# U_model.net
KiCad netlist of a schematic drawn in Altium Designer
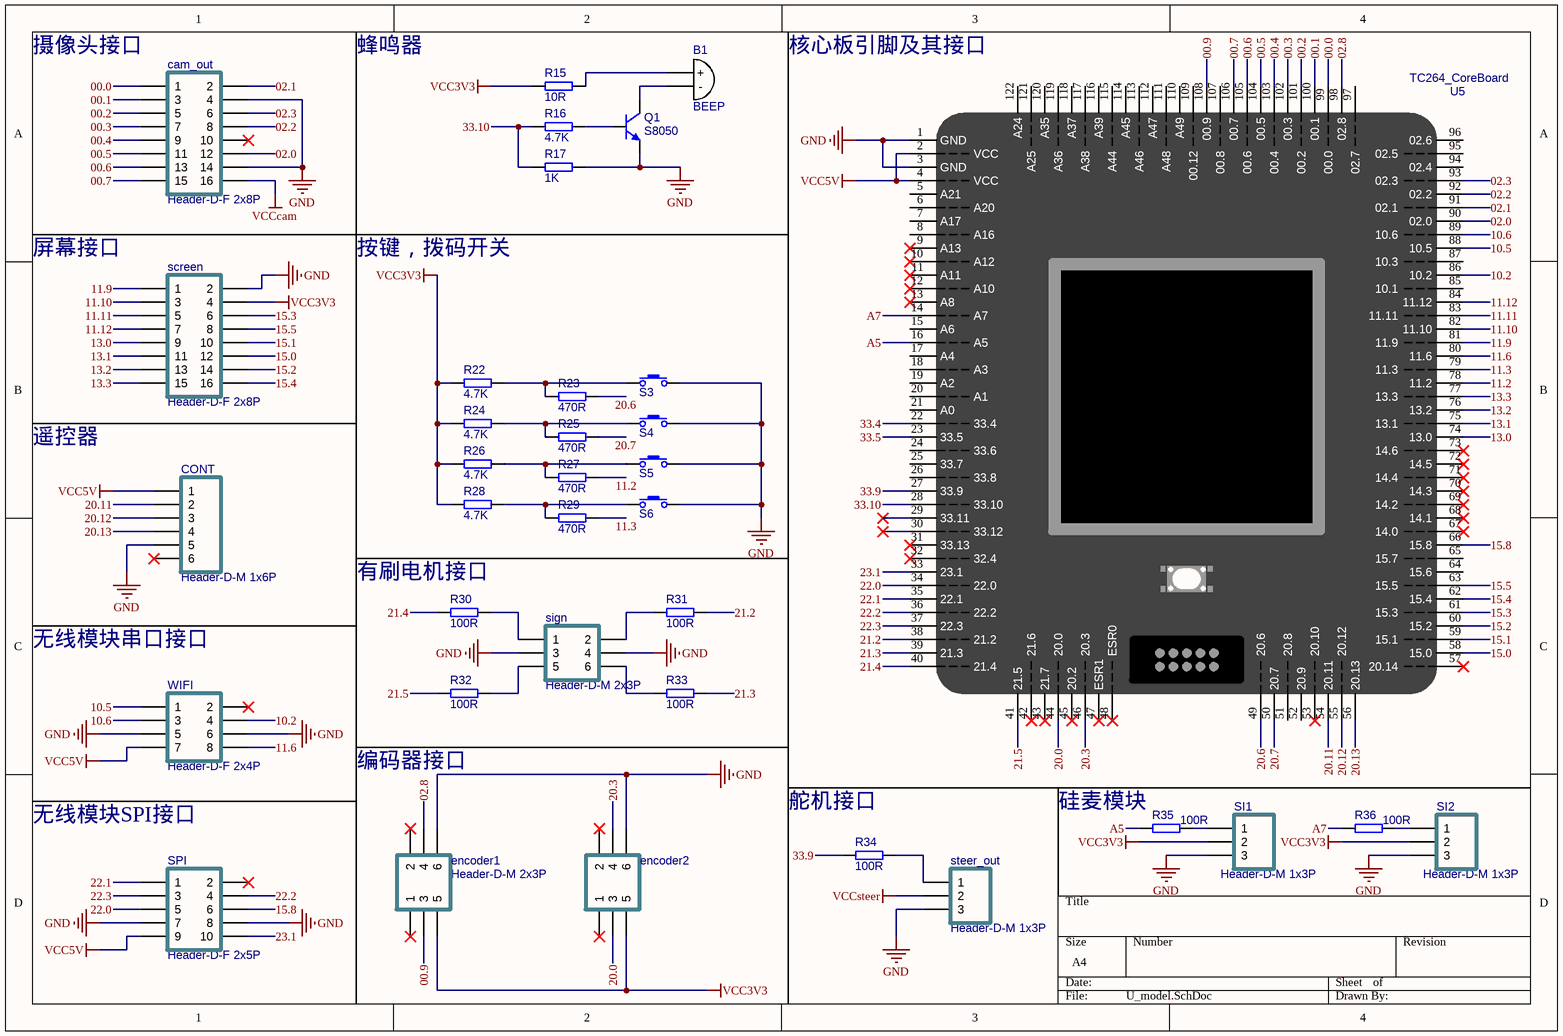
[diagram p0: U_model.SchDoc]

(export (version "E")
  (design (tool "Eeschema 10.0.6"))
  (components
    (comp (ref "B1")
      (value "BEEP")
      (footprint "BEEP 9x5.5mm")
      (description "蜂鸣器")
      (libsource (lib "TC264_主板_V2.6") (part "BEEP"))
    )
    (comp (ref "cam_out")
      (value "Header-D-F 2x8P")
      (footprint "HDR2X8-F")
      (description "2x8pin, 直插, 双排座")
      (libsource (lib "TC264_主板_V2.6") (part "Header-D-F 2x8P"))
    )
    (comp (ref "CONT")
      (value "Header-D-M 1x6P")
      (footprint "HDR1X6-M")
      (description "1x6pin, 直插, 排针")
      (libsource (lib "TC264_主板_V2.6") (part "Header-D-M 1x6P"))
    )
    (comp (ref "encoder1")
      (value "Header-D-M 2x3P")
      (footprint "HDR2X3-M")
      (description "2x3pin, 直插, 双排针")
      (libsource (lib "TC264_主板_V2.6") (part "Header-D-M 2x3P"))
    )
    (comp (ref "encoder2")
      (value "~")
      (footprint "HDR2X3-M")
      (description "2x3pin, 直插, 双排针")
      (libsource (lib "TC264_主板_V2.6") (part "Header-D-M 2x3P"))
    )
    (comp (ref "Q1")
      (value "S8050")
      (footprint "SOT-23")
      (description "NPN 三极管")
      (fields (field (name "PARTNUMBER") "S8050") (field (name "PUBLISHER") "Altium Limited"))
      (libsource (lib "TC264_主板_V2.6") (part "NPN S8050"))
    )
    (comp (ref "R15")
      (value "10R")
      (footprint "RESC1608[0603]S-N")
      (description "贴片电阻")
      (fields (field (name "POWER") "1/8W") (field (name "TOLERANCE") "±1%"))
      (libsource (lib "TC264_主板_V2.6") (part "Res-Chip_10"))
    )
    (comp (ref "R16")
      (value "4.7K")
      (footprint "RESC1608[0603]S-N")
      (description "贴片电阻")
      (fields (field (name "POWER") "1/8W") (field (name "TOLERANCE") "±1%"))
      (libsource (lib "TC264_主板_V2.6") (part "Res-Chip_3"))
    )
    (comp (ref "R17")
      (value "1K")
      (footprint "RESC1608[0603]S-N")
      (description "贴片电阻")
      (fields (field (name "POWER") "1/8W") (field (name "TOLERANCE") "±1%"))
      (libsource (lib "TC264_主板_V2.6") (part "Res-Chip_11"))
    )
    (comp (ref "R22")
      (value "4.7K")
      (footprint "RESC1608[0603]S-N")
      (description "贴片电阻")
      (fields (field (name "POWER") "1/8W") (field (name "TOLERANCE") "±1%"))
      (libsource (lib "TC264_主板_V2.6") (part "Res-Chip_3"))
    )
    (comp (ref "R23")
      (value "470R")
      (footprint "RESC1608[0603]S-N")
      (description "贴片电阻")
      (fields (field (name "POWER") "1/8W") (field (name "TOLERANCE") "±1%"))
      (libsource (lib "TC264_主板_V2.6") (part "Res-Chip_12"))
    )
    (comp (ref "R24")
      (value "4.7K")
      (footprint "RESC1608[0603]S-N")
      (description "贴片电阻")
      (fields (field (name "POWER") "1/8W") (field (name "TOLERANCE") "±1%"))
      (libsource (lib "TC264_主板_V2.6") (part "Res-Chip_3"))
    )
    (comp (ref "R25")
      (value "470R")
      (footprint "RESC1608[0603]S-N")
      (description "贴片电阻")
      (fields (field (name "POWER") "1/8W") (field (name "TOLERANCE") "±1%"))
      (libsource (lib "TC264_主板_V2.6") (part "Res-Chip_12"))
    )
    (comp (ref "R26")
      (value "4.7K")
      (footprint "RESC1608[0603]S-N")
      (description "贴片电阻")
      (fields (field (name "POWER") "1/8W") (field (name "TOLERANCE") "±1%"))
      (libsource (lib "TC264_主板_V2.6") (part "Res-Chip_3"))
    )
    (comp (ref "R27")
      (value "470R")
      (footprint "RESC1608[0603]S-N")
      (description "贴片电阻")
      (fields (field (name "POWER") "1/8W") (field (name "TOLERANCE") "±1%"))
      (libsource (lib "TC264_主板_V2.6") (part "Res-Chip_12"))
    )
    (comp (ref "R28")
      (value "4.7K")
      (footprint "RESC1608[0603]S-N")
      (description "贴片电阻")
      (fields (field (name "POWER") "1/8W") (field (name "TOLERANCE") "±1%"))
      (libsource (lib "TC264_主板_V2.6") (part "Res-Chip_3"))
    )
    (comp (ref "R29")
      (value "470R")
      (footprint "RESC1608[0603]S-N")
      (description "贴片电阻")
      (fields (field (name "POWER") "1/8W") (field (name "TOLERANCE") "±1%"))
      (libsource (lib "TC264_主板_V2.6") (part "Res-Chip_12"))
    )
    (comp (ref "R30")
      (value "100R")
      (footprint "RESC1608[0603]S-N")
      (description "贴片电阻")
      (fields (field (name "POWER") "1/8W") (field (name "TOLERANCE") "±1%"))
      (libsource (lib "TC264_主板_V2.6") (part "Res-Chip_9"))
    )
    (comp (ref "R31")
      (value "100R")
      (footprint "RESC1608[0603]S-N")
      (description "贴片电阻")
      (fields (field (name "POWER") "1/8W") (field (name "TOLERANCE") "±1%"))
      (libsource (lib "TC264_主板_V2.6") (part "Res-Chip_9"))
    )
    (comp (ref "R32")
      (value "100R")
      (footprint "RESC1608[0603]S-N")
      (description "贴片电阻")
      (fields (field (name "POWER") "1/8W") (field (name "TOLERANCE") "±1%"))
      (libsource (lib "TC264_主板_V2.6") (part "Res-Chip_9"))
    )
    (comp (ref "R33")
      (value "100R")
      (footprint "RESC1608[0603]S-N")
      (description "贴片电阻")
      (fields (field (name "POWER") "1/8W") (field (name "TOLERANCE") "±1%"))
      (libsource (lib "TC264_主板_V2.6") (part "Res-Chip_9"))
    )
    (comp (ref "R34")
      (value "100R")
      (footprint "RESC1608[0603]S-N")
      (description "贴片电阻")
      (fields (field (name "POWER") "1/8W") (field (name "TOLERANCE") "±1%"))
      (libsource (lib "TC264_主板_V2.6") (part "Res-Chip_9"))
    )
    (comp (ref "R35")
      (value "100R")
      (footprint "RESC1608[0603]S-N")
      (description "贴片电阻")
      (fields (field (name "POWER") "1/8W") (field (name "TOLERANCE") "±1%"))
      (libsource (lib "TC264_主板_V2.6") (part "Res-Chip_9"))
    )
    (comp (ref "R36")
      (value "100R")
      (footprint "RESC1608[0603]S-N")
      (description "贴片电阻")
      (fields (field (name "POWER") "1/8W") (field (name "TOLERANCE") "±1%"))
      (libsource (lib "TC264_主板_V2.6") (part "Res-Chip_9"))
    )
    (comp (ref "S3")
      (value "Button")
      (footprint "PTS810-3*4-CurvePin")
      (description "按键")
      (fields (field (name "PUBLISHER") "Altium Limited"))
      (libsource (lib "TC264_主板_V2.6") (part "KEY"))
    )
    (comp (ref "S4")
      (value "Button")
      (footprint "PTS810-3*4-CurvePin")
      (description "按键")
      (fields (field (name "PUBLISHER") "Altium Limited"))
      (libsource (lib "TC264_主板_V2.6") (part "KEY"))
    )
    (comp (ref "S5")
      (value "Button")
      (footprint "PTS810-3*4-CurvePin")
      (description "按键")
      (fields (field (name "PUBLISHER") "Altium Limited"))
      (libsource (lib "TC264_主板_V2.6") (part "KEY"))
    )
    (comp (ref "S6")
      (value "Button")
      (footprint "PTS810-3*4-CurvePin")
      (description "按键")
      (fields (field (name "PUBLISHER") "Altium Limited"))
      (libsource (lib "TC264_主板_V2.6") (part "KEY"))
    )
    (comp (ref "screen")
      (value "Header-D-F 2x8P")
      (footprint "HDR2X8-F")
      (description "2x8pin, 直插, 双排座")
      (libsource (lib "TC264_主板_V2.6") (part "Header-D-F 2x8P"))
    )
    (comp (ref "SI1")
      (value "Header-D-M 1x3P")
      (footprint "HDR1X3-M")
      (description "1x3pin, 直插, 排针")
      (libsource (lib "TC264_主板_V2.6") (part "Header-D-M 1x3P"))
    )
    (comp (ref "SI2")
      (value "Header-D-M 1x3P")
      (footprint "HDR1X3-M")
      (description "1x3pin, 直插, 排针")
      (libsource (lib "TC264_主板_V2.6") (part "Header-D-M 1x3P"))
    )
    (comp (ref "sign")
      (value "Header-D-M 2x3P")
      (footprint "HDR2X3-M")
      (description "2x3pin, 直插, 双排针")
      (libsource (lib "") (part "Header-D-M 2x3P_1"))
    )
    (comp (ref "SPI")
      (value "Header-D-F 2x5P")
      (footprint "HDR2X5-F")
      (description "2x5pin, 直插, 双排座")
      (libsource (lib "TC264_主板_V2.6") (part "Header-D-F 2x5P"))
    )
    (comp (ref "steer_out")
      (value "Header-D-M 1x3P")
      (footprint "HDR1X3-M")
      (description "1x3pin, 直插, 排针")
      (libsource (lib "TC264_主板_V2.6") (part "Header-D-M 1x3P"))
    )
    (comp (ref "U5")
      (value "TC264_CoreBoard")
      (footprint "TC264_CoreBoard")
      (description "逐飞科技TC264核心板")
      (libsource (lib "TC264_主板_V2.6") (part "TC264_CoreBoard"))
    )
    (comp (ref "WIFI")
      (value "Header-D-F 2x4P")
      (footprint "HDR2X4-F")
      (description "2x4pin, 直插, 双排座")
      (libsource (lib "TC264_主板_V2.6") (part "Header-D-F 2x4P"))
    )
  )
  (nets
    (net (code "1") (name "/00.0") (class "Default")
      (node (ref "U5") (pin "99") (pinfunction "00.0_99") (pintype "passive"))
      (node (ref "cam_out") (pin "1") (pinfunction "1_1") (pintype "passive"))
    )
    (net (code "2") (name "/00.1") (class "Default")
      (node (ref "U5") (pin "100") (pinfunction "00.1_100") (pintype "passive"))
      (node (ref "cam_out") (pin "3") (pinfunction "3_3") (pintype "passive"))
    )
    (net (code "3") (name "/00.2") (class "Default")
      (node (ref "U5") (pin "101") (pinfunction "00.2_101") (pintype "passive"))
      (node (ref "cam_out") (pin "5") (pinfunction "5_5") (pintype "passive"))
    )
    (net (code "4") (name "/00.3") (class "Default")
      (node (ref "U5") (pin "102") (pinfunction "00.3_102") (pintype "passive"))
      (node (ref "cam_out") (pin "7") (pinfunction "7_7") (pintype "passive"))
    )
    (net (code "5") (name "/00.4") (class "Default")
      (node (ref "U5") (pin "103") (pinfunction "00.4_103") (pintype "passive"))
      (node (ref "cam_out") (pin "9") (pinfunction "9_9") (pintype "passive"))
    )
    (net (code "6") (name "/00.5") (class "Default")
      (node (ref "U5") (pin "104") (pinfunction "00.5_104") (pintype "passive"))
      (node (ref "cam_out") (pin "11") (pinfunction "11_11") (pintype "passive"))
    )
    (net (code "7") (name "/00.6") (class "Default")
      (node (ref "U5") (pin "105") (pinfunction "00.6_105") (pintype "passive"))
      (node (ref "cam_out") (pin "13") (pinfunction "13_13") (pintype "passive"))
    )
    (net (code "8") (name "/00.7") (class "Default")
      (node (ref "U5") (pin "106") (pinfunction "00.7_106") (pintype "passive"))
      (node (ref "cam_out") (pin "15") (pinfunction "15_15") (pintype "passive"))
    )
    (net (code "9") (name "/00.9") (class "Default")
      (node (ref "U5") (pin "108") (pinfunction "00.9_108") (pintype "passive"))
      (node (ref "encoder1") (pin "3") (pinfunction "3_3") (pintype "passive"))
    )
    (net (code "10") (name "/02.0") (class "Default")
      (node (ref "U5") (pin "90") (pinfunction "02.0_90") (pintype "passive"))
      (node (ref "cam_out") (pin "12") (pinfunction "12_12") (pintype "passive"))
    )
    (net (code "11") (name "/02.1") (class "Default")
      (node (ref "U5") (pin "91") (pinfunction "02.1_91") (pintype "passive"))
      (node (ref "cam_out") (pin "2") (pinfunction "2_2") (pintype "passive"))
    )
    (net (code "12") (name "/02.2") (class "Default")
      (node (ref "U5") (pin "92") (pinfunction "02.2_92") (pintype "passive"))
      (node (ref "cam_out") (pin "8") (pinfunction "8_8") (pintype "passive"))
    )
    (net (code "13") (name "/02.3") (class "Default")
      (node (ref "U5") (pin "93") (pinfunction "02.3_93") (pintype "passive"))
      (node (ref "cam_out") (pin "6") (pinfunction "6_6") (pintype "passive"))
    )
    (net (code "14") (name "/02.8") (class "Default")
      (node (ref "U5") (pin "98") (pinfunction "02.8_98") (pintype "passive"))
      (node (ref "encoder1") (pin "4") (pinfunction "4_4") (pintype "passive"))
    )
    (net (code "15") (name "/10.2") (class "Default")
      (node (ref "U5") (pin "86") (pinfunction "10.2_86") (pintype "passive"))
      (node (ref "WIFI") (pin "4") (pinfunction "4_4") (pintype "passive"))
    )
    (net (code "16") (name "/10.5") (class "Default")
      (node (ref "U5") (pin "88") (pinfunction "10.5_88") (pintype "passive"))
      (node (ref "WIFI") (pin "1") (pinfunction "1_1") (pintype "passive"))
    )
    (net (code "17") (name "/10.6") (class "Default")
      (node (ref "U5") (pin "89") (pinfunction "10.6_89") (pintype "passive"))
      (node (ref "WIFI") (pin "3") (pinfunction "3_3") (pintype "passive"))
    )
    (net (code "18") (name "/11.2") (class "Default")
      (node (ref "R27") (pin "2") (pinfunction "2_2") (pintype "passive"))
      (node (ref "U5") (pin "78") (pinfunction "11.2_78") (pintype "passive"))
    )
    (net (code "19") (name "/11.3") (class "Default")
      (node (ref "R29") (pin "2") (pinfunction "2_2") (pintype "passive"))
      (node (ref "U5") (pin "79") (pinfunction "11.3_79") (pintype "passive"))
    )
    (net (code "20") (name "/11.6") (class "Default")
      (node (ref "U5") (pin "80") (pinfunction "11.6_80") (pintype "passive"))
      (node (ref "WIFI") (pin "8") (pinfunction "8_8") (pintype "passive"))
    )
    (net (code "21") (name "/11.9") (class "Default")
      (node (ref "U5") (pin "81") (pinfunction "11.9_81") (pintype "passive"))
      (node (ref "screen") (pin "1") (pinfunction "1_1") (pintype "passive"))
    )
    (net (code "22") (name "/11.10") (class "Default")
      (node (ref "U5") (pin "82") (pinfunction "11.10_82") (pintype "passive"))
      (node (ref "screen") (pin "3") (pinfunction "3_3") (pintype "passive"))
    )
    (net (code "23") (name "/11.11") (class "Default")
      (node (ref "U5") (pin "83") (pinfunction "11.11_83") (pintype "passive"))
      (node (ref "screen") (pin "5") (pinfunction "5_5") (pintype "passive"))
    )
    (net (code "24") (name "/11.12") (class "Default")
      (node (ref "U5") (pin "84") (pinfunction "11.12_84") (pintype "passive"))
      (node (ref "screen") (pin "7") (pinfunction "7_7") (pintype "passive"))
    )
    (net (code "25") (name "/13.0") (class "Default")
      (node (ref "U5") (pin "74") (pinfunction "13.0_74") (pintype "passive"))
      (node (ref "screen") (pin "9") (pinfunction "9_9") (pintype "passive"))
    )
    (net (code "26") (name "/13.1") (class "Default")
      (node (ref "U5") (pin "75") (pinfunction "13.1_75") (pintype "passive"))
      (node (ref "screen") (pin "11") (pinfunction "11_11") (pintype "passive"))
    )
    (net (code "27") (name "/13.2") (class "Default")
      (node (ref "U5") (pin "76") (pinfunction "13.2_76") (pintype "passive"))
      (node (ref "screen") (pin "13") (pinfunction "13_13") (pintype "passive"))
    )
    (net (code "28") (name "/13.3") (class "Default")
      (node (ref "U5") (pin "77") (pinfunction "13.3_77") (pintype "passive"))
      (node (ref "screen") (pin "15") (pinfunction "15_15") (pintype "passive"))
    )
    (net (code "29") (name "/15.0") (class "Default")
      (node (ref "U5") (pin "58") (pinfunction "15.0_58") (pintype "passive"))
      (node (ref "screen") (pin "12") (pinfunction "12_12") (pintype "passive"))
    )
    (net (code "30") (name "/15.1") (class "Default")
      (node (ref "U5") (pin "59") (pinfunction "15.1_59") (pintype "passive"))
      (node (ref "screen") (pin "10") (pinfunction "10_10") (pintype "passive"))
    )
    (net (code "31") (name "/15.2") (class "Default")
      (node (ref "U5") (pin "60") (pinfunction "15.2_60") (pintype "passive"))
      (node (ref "screen") (pin "14") (pinfunction "14_14") (pintype "passive"))
    )
    (net (code "32") (name "/15.3") (class "Default")
      (node (ref "U5") (pin "61") (pinfunction "15.3_61") (pintype "passive"))
      (node (ref "screen") (pin "6") (pinfunction "6_6") (pintype "passive"))
    )
    (net (code "33") (name "/15.4") (class "Default")
      (node (ref "U5") (pin "62") (pinfunction "15.4_62") (pintype "passive"))
      (node (ref "screen") (pin "16") (pinfunction "16_16") (pintype "passive"))
    )
    (net (code "34") (name "/15.5") (class "Default")
      (node (ref "U5") (pin "63") (pinfunction "15.5_63") (pintype "passive"))
      (node (ref "screen") (pin "8") (pinfunction "8_8") (pintype "passive"))
    )
    (net (code "35") (name "/15.8") (class "Default")
      (node (ref "SPI") (pin "6") (pinfunction "6_6") (pintype "passive"))
      (node (ref "U5") (pin "66") (pinfunction "15.8_66") (pintype "passive"))
    )
    (net (code "36") (name "/20.0") (class "Default")
      (node (ref "U5") (pin "44") (pinfunction "20.0_44") (pintype "passive"))
      (node (ref "encoder2") (pin "3") (pinfunction "3_3") (pintype "passive"))
    )
    (net (code "37") (name "/20.3") (class "Default")
      (node (ref "U5") (pin "46") (pinfunction "20.3_46") (pintype "passive"))
      (node (ref "encoder2") (pin "4") (pinfunction "4_4") (pintype "passive"))
    )
    (net (code "38") (name "/20.6") (class "Default")
      (node (ref "R23") (pin "2") (pinfunction "2_2") (pintype "passive"))
      (node (ref "U5") (pin "49") (pinfunction "20.6_49") (pintype "passive"))
    )
    (net (code "39") (name "/20.7") (class "Default")
      (node (ref "R25") (pin "2") (pinfunction "2_2") (pintype "passive"))
      (node (ref "U5") (pin "50") (pinfunction "20.7_50") (pintype "passive"))
    )
    (net (code "40") (name "/20.11") (class "Default")
      (node (ref "CONT") (pin "2") (pinfunction "2_2") (pintype "passive"))
      (node (ref "U5") (pin "54") (pinfunction "20.11_54") (pintype "passive"))
    )
    (net (code "41") (name "/20.12") (class "Default")
      (node (ref "CONT") (pin "3") (pinfunction "3_3") (pintype "passive"))
      (node (ref "U5") (pin "55") (pinfunction "20.12_55") (pintype "passive"))
    )
    (net (code "42") (name "/20.13") (class "Default")
      (node (ref "CONT") (pin "4") (pinfunction "4_4") (pintype "passive"))
      (node (ref "U5") (pin "56") (pinfunction "20.13_56") (pintype "passive"))
    )
    (net (code "43") (name "/21.2") (class "Default")
      (node (ref "R31") (pin "2") (pinfunction "2_2") (pintype "passive"))
      (node (ref "U5") (pin "38") (pinfunction "21.2_38") (pintype "passive"))
    )
    (net (code "44") (name "/21.3") (class "Default")
      (node (ref "R33") (pin "2") (pinfunction "2_2") (pintype "passive"))
      (node (ref "U5") (pin "39") (pinfunction "21.3_39") (pintype "passive"))
    )
    (net (code "45") (name "/21.4") (class "Default")
      (node (ref "R30") (pin "1") (pinfunction "1_1") (pintype "passive"))
      (node (ref "U5") (pin "40") (pinfunction "21.4_40") (pintype "passive"))
    )
    (net (code "46") (name "/21.5") (class "Default")
      (node (ref "R32") (pin "1") (pinfunction "1_1") (pintype "passive"))
      (node (ref "U5") (pin "41") (pinfunction "21.5_41") (pintype "passive"))
    )
    (net (code "47") (name "/22.0") (class "Default")
      (node (ref "SPI") (pin "5") (pinfunction "5_5") (pintype "passive"))
      (node (ref "U5") (pin "34") (pinfunction "22.0_34") (pintype "passive"))
    )
    (net (code "48") (name "/22.1") (class "Default")
      (node (ref "SPI") (pin "1") (pinfunction "1_1") (pintype "passive"))
      (node (ref "U5") (pin "35") (pinfunction "22.1_35") (pintype "passive"))
    )
    (net (code "49") (name "/22.2") (class "Default")
      (node (ref "SPI") (pin "4") (pinfunction "4_4") (pintype "passive"))
      (node (ref "U5") (pin "36") (pinfunction "22.2_36") (pintype "passive"))
    )
    (net (code "50") (name "/22.3") (class "Default")
      (node (ref "SPI") (pin "3") (pinfunction "3_3") (pintype "passive"))
      (node (ref "U5") (pin "37") (pinfunction "22.3_37") (pintype "passive"))
    )
    (net (code "51") (name "/23.1") (class "Default")
      (node (ref "SPI") (pin "10") (pinfunction "10_10") (pintype "passive"))
      (node (ref "U5") (pin "33") (pinfunction "23.1_33") (pintype "passive"))
    )
    (net (code "52") (name "/33.4") (class "Default")
      (node (ref "U5") (pin "22") (pinfunction "33.4_22") (pintype "passive"))
    )
    (net (code "53") (name "/33.5") (class "Default")
      (node (ref "U5") (pin "23") (pinfunction "33.5_23") (pintype "passive"))
    )
    (net (code "54") (name "/33.9") (class "Default")
      (node (ref "R34") (pin "1") (pinfunction "1_1") (pintype "passive"))
      (node (ref "U5") (pin "27") (pinfunction "33.9_27") (pintype "passive"))
    )
    (net (code "55") (name "/33.10") (class "Default")
      (node (ref "R16") (pin "1") (pinfunction "1_1") (pintype "passive"))
      (node (ref "R17") (pin "1") (pinfunction "1_1") (pintype "passive"))
      (node (ref "U5") (pin "28") (pinfunction "33.10_28") (pintype "passive"))
    )
    (net (code "56") (name "/A5") (class "Default")
      (node (ref "R35") (pin "1") (pinfunction "1_1") (pintype "passive"))
      (node (ref "U5") (pin "16") (pinfunction "A5_16") (pintype "passive"))
    )
    (net (code "57") (name "/A7") (class "Default")
      (node (ref "R36") (pin "1") (pinfunction "1_1") (pintype "passive"))
      (node (ref "U5") (pin "14") (pinfunction "A7_14") (pintype "passive"))
    )
    (net (code "58") (name "GND") (class "Default")
      (node (ref "CONT") (pin "5") (pinfunction "5_5") (pintype "passive"))
      (node (ref "Q1") (pin "2") (pinfunction "E_2") (pintype "passive"))
      (node (ref "R17") (pin "2") (pinfunction "2_2") (pintype "passive"))
      (node (ref "S3") (pin "1") (pinfunction "1_1") (pintype "passive"))
      (node (ref "S4") (pin "1") (pinfunction "1_1") (pintype "passive"))
      (node (ref "S5") (pin "1") (pinfunction "1_1") (pintype "passive"))
      (node (ref "S6") (pin "1") (pinfunction "1_1") (pintype "passive"))
      (node (ref "SI1") (pin "3") (pinfunction "3_3") (pintype "passive"))
      (node (ref "SI2") (pin "3") (pinfunction "3_3") (pintype "passive"))
      (node (ref "SPI") (pin "7") (pinfunction "7_7") (pintype "passive"))
      (node (ref "SPI") (pin "8") (pinfunction "8_8") (pintype "passive"))
      (node (ref "U5") (pin "1") (pinfunction "GND_1") (pintype "passive"))
      (node (ref "U5") (pin "3") (pinfunction "GND_3") (pintype "passive"))
      (node (ref "WIFI") (pin "5") (pinfunction "5_5") (pintype "passive"))
      (node (ref "WIFI") (pin "6") (pinfunction "6_6") (pintype "passive"))
      (node (ref "cam_out") (pin "14") (pinfunction "14_14") (pintype "passive"))
      (node (ref "cam_out") (pin "4") (pinfunction "4_4") (pintype "passive"))
      (node (ref "encoder1") (pin "6") (pinfunction "6_6") (pintype "passive"))
      (node (ref "encoder2") (pin "6") (pinfunction "6_6") (pintype "passive"))
      (node (ref "screen") (pin "2") (pinfunction "2_2") (pintype "passive"))
      (node (ref "sign") (pin "3") (pinfunction "3_3") (pintype "passive"))
      (node (ref "sign") (pin "4") (pinfunction "4_4") (pintype "passive"))
      (node (ref "steer_out") (pin "3") (pinfunction "3_3") (pintype "passive"))
    )
    (net (code "59") (name "Net-(B1-+)") (class "Default")
      (node (ref "B1") (pin "1") (pinfunction "+_1") (pintype "passive"))
      (node (ref "R15") (pin "2") (pinfunction "2_2") (pintype "passive"))
    )
    (net (code "60") (name "Net-(B1--)") (class "Default")
      (node (ref "B1") (pin "2") (pinfunction "-_2") (pintype "passive"))
      (node (ref "Q1") (pin "3") (pinfunction "C_3") (pintype "passive"))
    )
    (net (code "61") (name "Net-(Q1-B)") (class "Default")
      (node (ref "Q1") (pin "1") (pinfunction "B_1") (pintype "passive"))
      (node (ref "R16") (pin "2") (pinfunction "2_2") (pintype "passive"))
    )
    (net (code "62") (name "Net-(R22-Pad2)") (class "Default")
      (node (ref "R22") (pin "2") (pinfunction "2_2") (pintype "passive"))
      (node (ref "R23") (pin "1") (pinfunction "1_1") (pintype "passive"))
      (node (ref "S3") (pin "2") (pinfunction "2_2") (pintype "passive"))
    )
    (net (code "63") (name "Net-(R24-Pad2)") (class "Default")
      (node (ref "R24") (pin "2") (pinfunction "2_2") (pintype "passive"))
      (node (ref "R25") (pin "1") (pinfunction "1_1") (pintype "passive"))
      (node (ref "S4") (pin "2") (pinfunction "2_2") (pintype "passive"))
    )
    (net (code "64") (name "Net-(R26-Pad2)") (class "Default")
      (node (ref "R26") (pin "2") (pinfunction "2_2") (pintype "passive"))
      (node (ref "R27") (pin "1") (pinfunction "1_1") (pintype "passive"))
      (node (ref "S5") (pin "2") (pinfunction "2_2") (pintype "passive"))
    )
    (net (code "65") (name "Net-(R28-Pad2)") (class "Default")
      (node (ref "R28") (pin "2") (pinfunction "2_2") (pintype "passive"))
      (node (ref "R29") (pin "1") (pinfunction "1_1") (pintype "passive"))
      (node (ref "S6") (pin "2") (pinfunction "2_2") (pintype "passive"))
    )
    (net (code "66") (name "Net-(R30-Pad2)") (class "Default")
      (node (ref "R30") (pin "2") (pinfunction "2_2") (pintype "passive"))
      (node (ref "sign") (pin "1") (pinfunction "1_1") (pintype "passive"))
    )
    (net (code "67") (name "Net-(R31-Pad1)") (class "Default")
      (node (ref "R31") (pin "1") (pinfunction "1_1") (pintype "passive"))
      (node (ref "sign") (pin "2") (pinfunction "2_2") (pintype "passive"))
    )
    (net (code "68") (name "Net-(R32-Pad2)") (class "Default")
      (node (ref "R32") (pin "2") (pinfunction "2_2") (pintype "passive"))
      (node (ref "sign") (pin "5") (pinfunction "5_5") (pintype "passive"))
    )
    (net (code "69") (name "Net-(R33-Pad1)") (class "Default")
      (node (ref "R33") (pin "1") (pinfunction "1_1") (pintype "passive"))
      (node (ref "sign") (pin "6") (pinfunction "6_6") (pintype "passive"))
    )
    (net (code "70") (name "Net-(R34-Pad2)") (class "Default")
      (node (ref "R34") (pin "2") (pinfunction "2_2") (pintype "passive"))
      (node (ref "steer_out") (pin "1") (pinfunction "1_1") (pintype "passive"))
    )
    (net (code "71") (name "Net-(R35-Pad2)") (class "Default")
      (node (ref "R35") (pin "2") (pinfunction "2_2") (pintype "passive"))
      (node (ref "SI1") (pin "1") (pinfunction "1_1") (pintype "passive"))
    )
    (net (code "72") (name "Net-(R36-Pad2)") (class "Default")
      (node (ref "R36") (pin "2") (pinfunction "2_2") (pintype "passive"))
      (node (ref "SI2") (pin "1") (pinfunction "1_1") (pintype "passive"))
    )
    (net (code "73") (name "VCC3V3") (class "Default")
      (node (ref "R15") (pin "1") (pinfunction "1_1") (pintype "passive"))
      (node (ref "R22") (pin "1") (pinfunction "1_1") (pintype "passive"))
      (node (ref "R24") (pin "1") (pinfunction "1_1") (pintype "passive"))
      (node (ref "R26") (pin "1") (pinfunction "1_1") (pintype "passive"))
      (node (ref "R28") (pin "1") (pinfunction "1_1") (pintype "passive"))
      (node (ref "SI1") (pin "2") (pinfunction "2_2") (pintype "passive"))
      (node (ref "SI2") (pin "2") (pinfunction "2_2") (pintype "passive"))
      (node (ref "encoder1") (pin "5") (pinfunction "5_5") (pintype "passive"))
      (node (ref "encoder2") (pin "5") (pinfunction "5_5") (pintype "passive"))
      (node (ref "screen") (pin "4") (pinfunction "4_4") (pintype "passive"))
    )
    (net (code "74") (name "VCC5V") (class "Default")
      (node (ref "CONT") (pin "1") (pinfunction "1_1") (pintype "passive"))
      (node (ref "SPI") (pin "9") (pinfunction "9_9") (pintype "passive"))
      (node (ref "U5") (pin "2") (pinfunction "VCC_2") (pintype "passive"))
      (node (ref "U5") (pin "4") (pinfunction "VCC_4") (pintype "passive"))
      (node (ref "WIFI") (pin "7") (pinfunction "7_7") (pintype "passive"))
    )
    (net (code "75") (name "VCCcam") (class "Default")
      (node (ref "cam_out") (pin "16") (pinfunction "16_16") (pintype "passive"))
    )
    (net (code "76") (name "VCCsteer") (class "Default")
      (node (ref "steer_out") (pin "2") (pinfunction "2_2") (pintype "passive"))
    )
    (net (code "77") (name "unconnected-(CONT-Pad6)") (class "Default")
      (node (ref "CONT") (pin "6") (pinfunction "6_6") (pintype "passive+no_connect"))
    )
    (net (code "78") (name "unconnected-(SPI-Pad2)") (class "Default")
      (node (ref "SPI") (pin "2") (pinfunction "2_2") (pintype "passive+no_connect"))
    )
    (net (code "79") (name "unconnected-(U5-00.8-Pad107)") (class "Default")
      (node (ref "U5") (pin "107") (pinfunction "00.8_107") (pintype "passive"))
    )
    (net (code "80") (name "unconnected-(U5-00.12-Pad109)") (class "Default")
      (node (ref "U5") (pin "109") (pinfunction "00.12_109") (pintype "passive"))
    )
    (net (code "81") (name "unconnected-(U5-02.4-Pad94)") (class "Default")
      (node (ref "U5") (pin "94") (pinfunction "02.4_94") (pintype "passive"))
    )
    (net (code "82") (name "unconnected-(U5-02.5-Pad95)") (class "Default")
      (node (ref "U5") (pin "95") (pinfunction "02.5_95") (pintype "passive"))
    )
    (net (code "83") (name "unconnected-(U5-02.6-Pad96)") (class "Default")
      (node (ref "U5") (pin "96") (pinfunction "02.6_96") (pintype "passive"))
    )
    (net (code "84") (name "unconnected-(U5-02.7-Pad97)") (class "Default")
      (node (ref "U5") (pin "97") (pinfunction "02.7_97") (pintype "passive"))
    )
    (net (code "85") (name "unconnected-(U5-10.1-Pad85)") (class "Default")
      (node (ref "U5") (pin "85") (pinfunction "10.1_85") (pintype "passive"))
    )
    (net (code "86") (name "unconnected-(U5-10.3-Pad87)") (class "Default")
      (node (ref "U5") (pin "87") (pinfunction "10.3_87") (pintype "passive"))
    )
    (net (code "87") (name "unconnected-(U5-14.0-Pad67)") (class "Default")
      (node (ref "U5") (pin "67") (pinfunction "14.0_67") (pintype "passive+no_connect"))
    )
    (net (code "88") (name "unconnected-(U5-14.1-Pad68)") (class "Default")
      (node (ref "U5") (pin "68") (pinfunction "14.1_68") (pintype "passive+no_connect"))
    )
    (net (code "89") (name "unconnected-(U5-14.2-Pad69)") (class "Default")
      (node (ref "U5") (pin "69") (pinfunction "14.2_69") (pintype "passive+no_connect"))
    )
    (net (code "90") (name "unconnected-(U5-14.3-Pad70)") (class "Default")
      (node (ref "U5") (pin "70") (pinfunction "14.3_70") (pintype "passive+no_connect"))
    )
    (net (code "91") (name "unconnected-(U5-14.4-Pad71)") (class "Default")
      (node (ref "U5") (pin "71") (pinfunction "14.4_71") (pintype "passive+no_connect"))
    )
    (net (code "92") (name "unconnected-(U5-14.5-Pad72)") (class "Default")
      (node (ref "U5") (pin "72") (pinfunction "14.5_72") (pintype "passive+no_connect"))
    )
    (net (code "93") (name "unconnected-(U5-14.6-Pad73)") (class "Default")
      (node (ref "U5") (pin "73") (pinfunction "14.6_73") (pintype "passive+no_connect"))
    )
    (net (code "94") (name "unconnected-(U5-15.6-Pad64)") (class "Default")
      (node (ref "U5") (pin "64") (pinfunction "15.6_64") (pintype "passive"))
    )
    (net (code "95") (name "unconnected-(U5-15.7-Pad65)") (class "Default")
      (node (ref "U5") (pin "65") (pinfunction "15.7_65") (pintype "passive"))
    )
    (net (code "96") (name "unconnected-(U5-20.2-Pad45)") (class "Default")
      (node (ref "U5") (pin "45") (pinfunction "20.2_45") (pintype "passive+no_connect"))
    )
    (net (code "97") (name "unconnected-(U5-20.8-Pad51)") (class "Default")
      (node (ref "U5") (pin "51") (pinfunction "20.8_51") (pintype "passive"))
    )
    (net (code "98") (name "unconnected-(U5-20.9-Pad52)") (class "Default")
      (node (ref "U5") (pin "52") (pinfunction "20.9_52") (pintype "passive"))
    )
    (net (code "99") (name "unconnected-(U5-20.10-Pad53)") (class "Default")
      (node (ref "U5") (pin "53") (pinfunction "20.10_53") (pintype "passive+no_connect"))
    )
    (net (code "100") (name "unconnected-(U5-20.14-Pad57)") (class "Default")
      (node (ref "U5") (pin "57") (pinfunction "20.14_57") (pintype "passive+no_connect"))
    )
    (net (code "101") (name "unconnected-(U5-21.6-Pad42)") (class "Default")
      (node (ref "U5") (pin "42") (pinfunction "21.6_42") (pintype "passive+no_connect"))
    )
    (net (code "102") (name "unconnected-(U5-21.7-Pad43)") (class "Default")
      (node (ref "U5") (pin "43") (pinfunction "21.7_43") (pintype "passive+no_connect"))
    )
    (net (code "103") (name "unconnected-(U5-32.4-Pad32)") (class "Default")
      (node (ref "U5") (pin "32") (pinfunction "32.4_32") (pintype "passive+no_connect"))
    )
    (net (code "104") (name "unconnected-(U5-33.6-Pad24)") (class "Default")
      (node (ref "U5") (pin "24") (pinfunction "33.6_24") (pintype "passive"))
    )
    (net (code "105") (name "unconnected-(U5-33.7-Pad25)") (class "Default")
      (node (ref "U5") (pin "25") (pinfunction "33.7_25") (pintype "passive"))
    )
    (net (code "106") (name "unconnected-(U5-33.8-Pad26)") (class "Default")
      (node (ref "U5") (pin "26") (pinfunction "33.8_26") (pintype "passive"))
    )
    (net (code "107") (name "unconnected-(U5-33.11-Pad29)") (class "Default")
      (node (ref "U5") (pin "29") (pinfunction "33.11_29") (pintype "passive+no_connect"))
    )
    (net (code "108") (name "unconnected-(U5-33.12-Pad30)") (class "Default")
      (node (ref "U5") (pin "30") (pinfunction "33.12_30") (pintype "passive+no_connect"))
    )
    (net (code "109") (name "unconnected-(U5-33.13-Pad31)") (class "Default")
      (node (ref "U5") (pin "31") (pinfunction "33.13_31") (pintype "passive+no_connect"))
    )
    (net (code "110") (name "unconnected-(U5-A0-Pad21)") (class "Default")
      (node (ref "U5") (pin "21") (pinfunction "A0_21") (pintype "passive"))
    )
    (net (code "111") (name "unconnected-(U5-A1-Pad20)") (class "Default")
      (node (ref "U5") (pin "20") (pinfunction "A1_20") (pintype "passive"))
    )
    (net (code "112") (name "unconnected-(U5-A2-Pad19)") (class "Default")
      (node (ref "U5") (pin "19") (pinfunction "A2_19") (pintype "passive"))
    )
    (net (code "113") (name "unconnected-(U5-A3-Pad18)") (class "Default")
      (node (ref "U5") (pin "18") (pinfunction "A3_18") (pintype "passive"))
    )
    (net (code "114") (name "unconnected-(U5-A4-Pad17)") (class "Default")
      (node (ref "U5") (pin "17") (pinfunction "A4_17") (pintype "passive"))
    )
    (net (code "115") (name "unconnected-(U5-A6-Pad15)") (class "Default")
      (node (ref "U5") (pin "15") (pinfunction "A6_15") (pintype "passive"))
    )
    (net (code "116") (name "unconnected-(U5-A8-Pad13)") (class "Default")
      (node (ref "U5") (pin "13") (pinfunction "A8_13") (pintype "passive+no_connect"))
    )
    (net (code "117") (name "unconnected-(U5-A10-Pad12)") (class "Default")
      (node (ref "U5") (pin "12") (pinfunction "A10_12") (pintype "passive+no_connect"))
    )
    (net (code "118") (name "unconnected-(U5-A11-Pad11)") (class "Default")
      (node (ref "U5") (pin "11") (pinfunction "A11_11") (pintype "passive+no_connect"))
    )
    (net (code "119") (name "unconnected-(U5-A12-Pad10)") (class "Default")
      (node (ref "U5") (pin "10") (pinfunction "A12_10") (pintype "passive+no_connect"))
    )
    (net (code "120") (name "unconnected-(U5-A13-Pad9)") (class "Default")
      (node (ref "U5") (pin "9") (pinfunction "A13_9") (pintype "passive+no_connect"))
    )
    (net (code "121") (name "unconnected-(U5-A16-Pad8)") (class "Default")
      (node (ref "U5") (pin "8") (pinfunction "A16_8") (pintype "passive"))
    )
    (net (code "122") (name "unconnected-(U5-A17-Pad7)") (class "Default")
      (node (ref "U5") (pin "7") (pinfunction "A17_7") (pintype "passive"))
    )
    (net (code "123") (name "unconnected-(U5-A20-Pad6)") (class "Default")
      (node (ref "U5") (pin "6") (pinfunction "A20_6") (pintype "passive"))
    )
    (net (code "124") (name "unconnected-(U5-A21-Pad5)") (class "Default")
      (node (ref "U5") (pin "5") (pinfunction "A21_5") (pintype "passive"))
    )
    (net (code "125") (name "unconnected-(U5-A24-Pad122)") (class "Default")
      (node (ref "U5") (pin "122") (pinfunction "A24_122") (pintype "passive"))
    )
    (net (code "126") (name "unconnected-(U5-A25-Pad121)") (class "Default")
      (node (ref "U5") (pin "121") (pinfunction "A25_121") (pintype "passive"))
    )
    (net (code "127") (name "unconnected-(U5-A35-Pad120)") (class "Default")
      (node (ref "U5") (pin "120") (pinfunction "A35_120") (pintype "passive"))
    )
    (net (code "128") (name "unconnected-(U5-A36-Pad119)") (class "Default")
      (node (ref "U5") (pin "119") (pinfunction "A36_119") (pintype "passive"))
    )
    (net (code "129") (name "unconnected-(U5-A37-Pad118)") (class "Default")
      (node (ref "U5") (pin "118") (pinfunction "A37_118") (pintype "passive"))
    )
    (net (code "130") (name "unconnected-(U5-A38-Pad117)") (class "Default")
      (node (ref "U5") (pin "117") (pinfunction "A38_117") (pintype "passive"))
    )
    (net (code "131") (name "unconnected-(U5-A39-Pad116)") (class "Default")
      (node (ref "U5") (pin "116") (pinfunction "A39_116") (pintype "passive"))
    )
    (net (code "132") (name "unconnected-(U5-A44-Pad115)") (class "Default")
      (node (ref "U5") (pin "115") (pinfunction "A44_115") (pintype "passive"))
    )
    (net (code "133") (name "unconnected-(U5-A45-Pad114)") (class "Default")
      (node (ref "U5") (pin "114") (pinfunction "A45_114") (pintype "passive"))
    )
    (net (code "134") (name "unconnected-(U5-A46-Pad113)") (class "Default")
      (node (ref "U5") (pin "113") (pinfunction "A46_113") (pintype "passive"))
    )
    (net (code "135") (name "unconnected-(U5-A47-Pad112)") (class "Default")
      (node (ref "U5") (pin "112") (pinfunction "A47_112") (pintype "passive"))
    )
    (net (code "136") (name "unconnected-(U5-A48-Pad111)") (class "Default")
      (node (ref "U5") (pin "111") (pinfunction "A48_111") (pintype "passive"))
    )
    (net (code "137") (name "unconnected-(U5-A49-Pad110)") (class "Default")
      (node (ref "U5") (pin "110") (pinfunction "A49_110") (pintype "passive"))
    )
    (net (code "138") (name "unconnected-(U5-ESR0-Pad48)") (class "Default")
      (node (ref "U5") (pin "48") (pinfunction "ESR0_48") (pintype "passive+no_connect"))
    )
    (net (code "139") (name "unconnected-(U5-ESR1-Pad47)") (class "Default")
      (node (ref "U5") (pin "47") (pinfunction "ESR1_47") (pintype "passive+no_connect"))
    )
    (net (code "140") (name "unconnected-(WIFI-Pad2)") (class "Default")
      (node (ref "WIFI") (pin "2") (pinfunction "2_2") (pintype "passive+no_connect"))
    )
    (net (code "141") (name "unconnected-(cam_out-Pad10)") (class "Default")
      (node (ref "cam_out") (pin "10") (pinfunction "10_10") (pintype "passive+no_connect"))
    )
    (net (code "142") (name "unconnected-(encoder1-Pad1)") (class "Default")
      (node (ref "encoder1") (pin "1") (pinfunction "1_1") (pintype "passive+no_connect"))
    )
    (net (code "143") (name "unconnected-(encoder1-Pad2)") (class "Default")
      (node (ref "encoder1") (pin "2") (pinfunction "2_2") (pintype "passive+no_connect"))
    )
    (net (code "144") (name "unconnected-(encoder2-Pad1)") (class "Default")
      (node (ref "encoder2") (pin "1") (pinfunction "1_1") (pintype "passive+no_connect"))
    )
    (net (code "145") (name "unconnected-(encoder2-Pad2)") (class "Default")
      (node (ref "encoder2") (pin "2") (pinfunction "2_2") (pintype "passive+no_connect"))
    )
  )
)
